# SCH_usb-hub_2024-08-06.net
KiCad netlist of a schematic drawn in EasyEDA
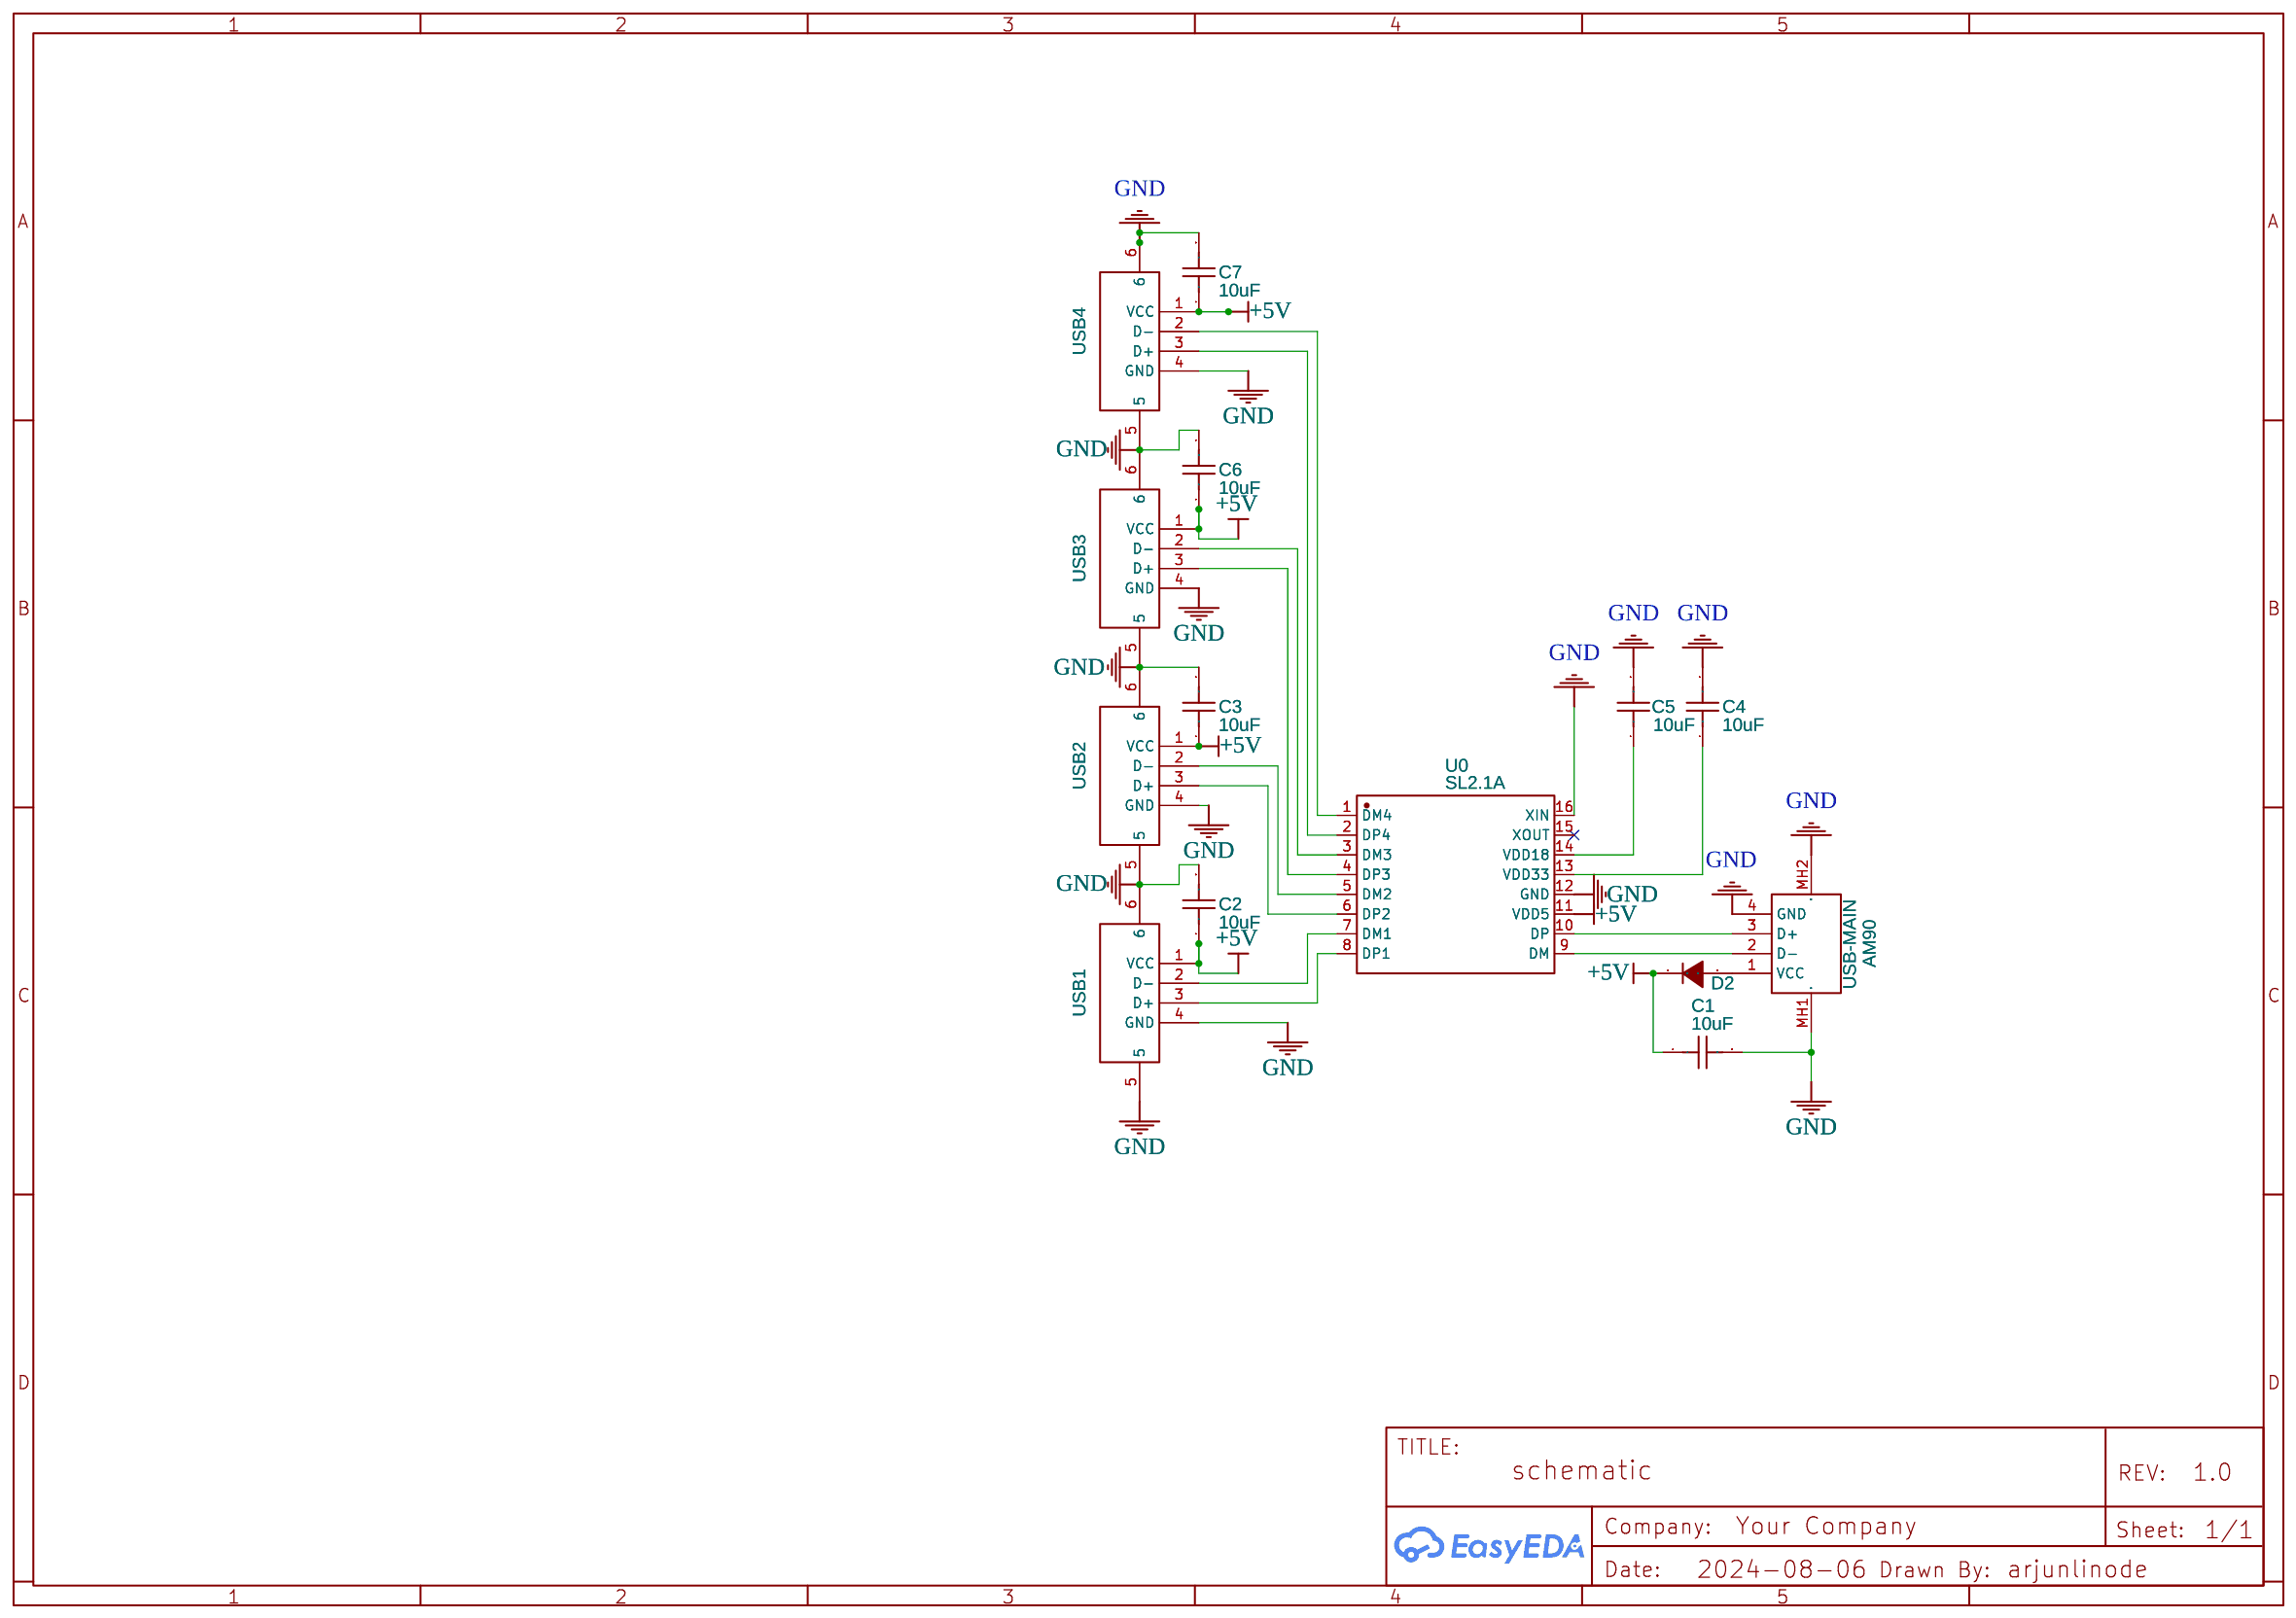
[diagram p0: schematic sheet]

(export (version "E")
  (design (tool "Eeschema 10.0.6"))
  (components
    (comp (ref "C1")
      (value "10uF")
      (fields
        (field (name "Manufacturer Part") "CL10A106KP8NNNC")
        (field (name "Manufacturer") "SAMSUNG(三星)")
      )
      (libsource (lib "") (part "CL10A106KP8NNNC"))
    )
    (comp (ref "C2")
      (value "10uF")
      (fields
        (field (name "Manufacturer Part") "CL10A106KP8NNNC")
        (field (name "Manufacturer") "SAMSUNG(三星)")
      )
      (libsource (lib "") (part "CL10A106KP8NNNC_1"))
    )
    (comp (ref "C3")
      (value "10uF")
      (fields
        (field (name "Manufacturer Part") "CL10A106KP8NNNC")
        (field (name "Manufacturer") "SAMSUNG(三星)")
      )
      (libsource (lib "") (part "CL10A106KP8NNNC_1"))
    )
    (comp (ref "C4")
      (value "10uF")
      (fields
        (field (name "Manufacturer Part") "CL10A106KP8NNNC")
        (field (name "Manufacturer") "SAMSUNG(三星)")
      )
      (libsource (lib "") (part "CL10A106KP8NNNC_1"))
    )
    (comp (ref "C5")
      (value "10uF")
      (fields
        (field (name "Manufacturer Part") "CL10A106KP8NNNC")
        (field (name "Manufacturer") "SAMSUNG(三星)")
      )
      (libsource (lib "") (part "CL10A106KP8NNNC_1"))
    )
    (comp (ref "C6")
      (value "10uF")
      (fields
        (field (name "Manufacturer Part") "CL10A106KP8NNNC")
        (field (name "Manufacturer") "SAMSUNG(三星)")
      )
      (libsource (lib "") (part "CL10A106KP8NNNC_1"))
    )
    (comp (ref "C7")
      (value "10uF")
      (fields
        (field (name "Manufacturer Part") "CL10A106KP8NNNC")
        (field (name "Manufacturer") "SAMSUNG(三星)")
      )
      (libsource (lib "") (part "CL10A106KP8NNNC_1"))
    )
    (comp (ref "D2")
      (value "NSR0320MW2T1G")
      (fields (field (name "Manufacturer") "onsemi(安森美)"))
      (libsource (lib "") (part "NSR0320MW2T1G"))
    )
    (comp (ref "U0")
      (value "SL2.1A")
      (fields (field (name "Manufacturer") "CoreChips(和芯润德)"))
      (libsource (lib "") (part "SL2.1A"))
    )
    (comp (ref "USB-MAIN")
      (value "AM90")
      (fields (field (name "Manufacturer") "SHOU HAN(首韩)"))
      (libsource (lib "") (part "AM90"))
    )
    (comp (ref "USB1")
      (value "USB-AF-90-14.4X13.6-H7.0-DIP")
      (fields (field (name "Manufacturer Part") "903-131A1011D10100") (field (name "Manufacturer") "精拓金"))
      (libsource (lib "") (part "USB-AF-90-14.4X13.6-H7.0-DIP"))
    )
    (comp (ref "USB2")
      (value "USB-AF-90-14.4X13.6-H7.0-DIP")
      (fields (field (name "Manufacturer Part") "903-131A1011D10100") (field (name "Manufacturer") "精拓金"))
      (libsource (lib "") (part "USB-AF-90-14.4X13.6-H7.0-DIP"))
    )
    (comp (ref "USB3")
      (value "USB-AF-90-14.4X13.6-H7.0-DIP")
      (fields (field (name "Manufacturer Part") "903-131A1011D10100") (field (name "Manufacturer") "精拓金"))
      (libsource (lib "") (part "USB-AF-90-14.4X13.6-H7.0-DIP"))
    )
    (comp (ref "USB4")
      (value "USB-AF-90-14.4X13.6-H7.0-DIP")
      (fields (field (name "Manufacturer Part") "903-131A1011D10100") (field (name "Manufacturer") "精拓金"))
      (libsource (lib "") (part "USB-AF-90-14.4X13.6-H7.0-DIP"))
    )
  )
  (nets
    (net (code "1") (name "+5V") (class "Default")
      (node (ref "C1") (pin "1") (pinfunction "1_1") (pintype "unspecified"))
      (node (ref "C2") (pin "1") (pinfunction "1_1") (pintype "unspecified"))
      (node (ref "C3") (pin "1") (pinfunction "1_1") (pintype "unspecified"))
      (node (ref "C6") (pin "1") (pinfunction "1_1") (pintype "unspecified"))
      (node (ref "C7") (pin "1") (pinfunction "1_1") (pintype "unspecified"))
      (node (ref "D2") (pin "1") (pinfunction "C_1") (pintype "unspecified"))
      (node (ref "U0") (pin "11") (pinfunction "VDD5_11") (pintype "unspecified"))
      (node (ref "USB1") (pin "1") (pinfunction "VCC_1") (pintype "unspecified"))
      (node (ref "USB2") (pin "1") (pinfunction "VCC_1") (pintype "unspecified"))
      (node (ref "USB3") (pin "1") (pinfunction "VCC_1") (pintype "unspecified"))
      (node (ref "USB4") (pin "1") (pinfunction "VCC_1") (pintype "unspecified"))
    )
    (net (code "2") (name "GND") (class "Default")
      (node (ref "C1") (pin "2") (pinfunction "2_2") (pintype "unspecified"))
      (node (ref "C2") (pin "2") (pinfunction "2_2") (pintype "unspecified"))
      (node (ref "C3") (pin "2") (pinfunction "2_2") (pintype "unspecified"))
      (node (ref "C4") (pin "2") (pinfunction "2_2") (pintype "unspecified"))
      (node (ref "C5") (pin "2") (pinfunction "2_2") (pintype "unspecified"))
      (node (ref "C6") (pin "2") (pinfunction "2_2") (pintype "unspecified"))
      (node (ref "C7") (pin "2") (pinfunction "2_2") (pintype "unspecified"))
      (node (ref "U0") (pin "12") (pinfunction "GND_12") (pintype "unspecified"))
      (node (ref "U0") (pin "16") (pinfunction "XIN_16") (pintype "unspecified"))
      (node (ref "USB-MAIN") (pin "4") (pinfunction "GND_4") (pintype "input"))
      (node (ref "USB-MAIN") (pin "MH1") (pinfunction "MH1_MH1") (pintype "unspecified"))
      (node (ref "USB-MAIN") (pin "MH2") (pinfunction "MH2_MH2") (pintype "unspecified"))
      (node (ref "USB1") (pin "4") (pinfunction "GND_4") (pintype "unspecified"))
      (node (ref "USB1") (pin "5") (pinfunction "5_5") (pintype "unspecified"))
      (node (ref "USB1") (pin "6") (pinfunction "6_6") (pintype "unspecified"))
      (node (ref "USB2") (pin "4") (pinfunction "GND_4") (pintype "unspecified"))
      (node (ref "USB2") (pin "5") (pinfunction "5_5") (pintype "unspecified"))
      (node (ref "USB2") (pin "6") (pinfunction "6_6") (pintype "unspecified"))
      (node (ref "USB3") (pin "4") (pinfunction "GND_4") (pintype "unspecified"))
      (node (ref "USB3") (pin "5") (pinfunction "5_5") (pintype "unspecified"))
      (node (ref "USB3") (pin "6") (pinfunction "6_6") (pintype "unspecified"))
      (node (ref "USB4") (pin "4") (pinfunction "GND_4") (pintype "unspecified"))
      (node (ref "USB4") (pin "5") (pinfunction "5_5") (pintype "unspecified"))
      (node (ref "USB4") (pin "6") (pinfunction "6_6") (pintype "unspecified"))
    )
    (net (code "3") (name "Net-(D2-A)") (class "Default")
      (node (ref "D2") (pin "2") (pinfunction "A_2") (pintype "unspecified"))
      (node (ref "USB-MAIN") (pin "1") (pinfunction "VCC_1") (pintype "input"))
    )
    (net (code "4") (name "Net-(U0-DM)") (class "Default")
      (node (ref "U0") (pin "9") (pinfunction "DM_9") (pintype "unspecified"))
      (node (ref "USB-MAIN") (pin "2") (pinfunction "D-_2") (pintype "input"))
    )
    (net (code "5") (name "Net-(U0-DM1)") (class "Default")
      (node (ref "U0") (pin "7") (pinfunction "DM1_7") (pintype "unspecified"))
      (node (ref "USB1") (pin "2") (pinfunction "D-_2") (pintype "unspecified"))
    )
    (net (code "6") (name "Net-(U0-DM2)") (class "Default")
      (node (ref "U0") (pin "5") (pinfunction "DM2_5") (pintype "unspecified"))
      (node (ref "USB2") (pin "2") (pinfunction "D-_2") (pintype "unspecified"))
    )
    (net (code "7") (name "Net-(U0-DM3)") (class "Default")
      (node (ref "U0") (pin "3") (pinfunction "DM3_3") (pintype "unspecified"))
      (node (ref "USB3") (pin "2") (pinfunction "D-_2") (pintype "unspecified"))
    )
    (net (code "8") (name "Net-(U0-DM4)") (class "Default")
      (node (ref "U0") (pin "1") (pinfunction "DM4_1") (pintype "unspecified"))
      (node (ref "USB4") (pin "2") (pinfunction "D-_2") (pintype "unspecified"))
    )
    (net (code "9") (name "Net-(U0-DP)") (class "Default")
      (node (ref "U0") (pin "10") (pinfunction "DP_10") (pintype "unspecified"))
      (node (ref "USB-MAIN") (pin "3") (pinfunction "D+_3") (pintype "input"))
    )
    (net (code "10") (name "Net-(U0-DP1)") (class "Default")
      (node (ref "U0") (pin "8") (pinfunction "DP1_8") (pintype "unspecified"))
      (node (ref "USB1") (pin "3") (pinfunction "D+_3") (pintype "unspecified"))
    )
    (net (code "11") (name "Net-(U0-DP2)") (class "Default")
      (node (ref "U0") (pin "6") (pinfunction "DP2_6") (pintype "unspecified"))
      (node (ref "USB2") (pin "3") (pinfunction "D+_3") (pintype "unspecified"))
    )
    (net (code "12") (name "Net-(U0-DP3)") (class "Default")
      (node (ref "U0") (pin "4") (pinfunction "DP3_4") (pintype "unspecified"))
      (node (ref "USB3") (pin "3") (pinfunction "D+_3") (pintype "unspecified"))
    )
    (net (code "13") (name "Net-(U0-DP4)") (class "Default")
      (node (ref "U0") (pin "2") (pinfunction "DP4_2") (pintype "unspecified"))
      (node (ref "USB4") (pin "3") (pinfunction "D+_3") (pintype "unspecified"))
    )
    (net (code "14") (name "Net-(U0-VDD18)") (class "Default")
      (node (ref "C5") (pin "1") (pinfunction "1_1") (pintype "unspecified"))
      (node (ref "U0") (pin "14") (pinfunction "VDD18_14") (pintype "unspecified"))
    )
    (net (code "15") (name "Net-(U0-VDD33)") (class "Default")
      (node (ref "C4") (pin "1") (pinfunction "1_1") (pintype "unspecified"))
      (node (ref "U0") (pin "13") (pinfunction "VDD33_13") (pintype "unspecified"))
    )
    (net (code "16") (name "unconnected-(U0-XOUT-Pad15)") (class "Default")
      (node (ref "U0") (pin "15") (pinfunction "XOUT_15") (pintype "unspecified+no_connect"))
    )
  )
)
